# CortexM3_dev.net
KiCad netlist of a schematic drawn in Altium Designer
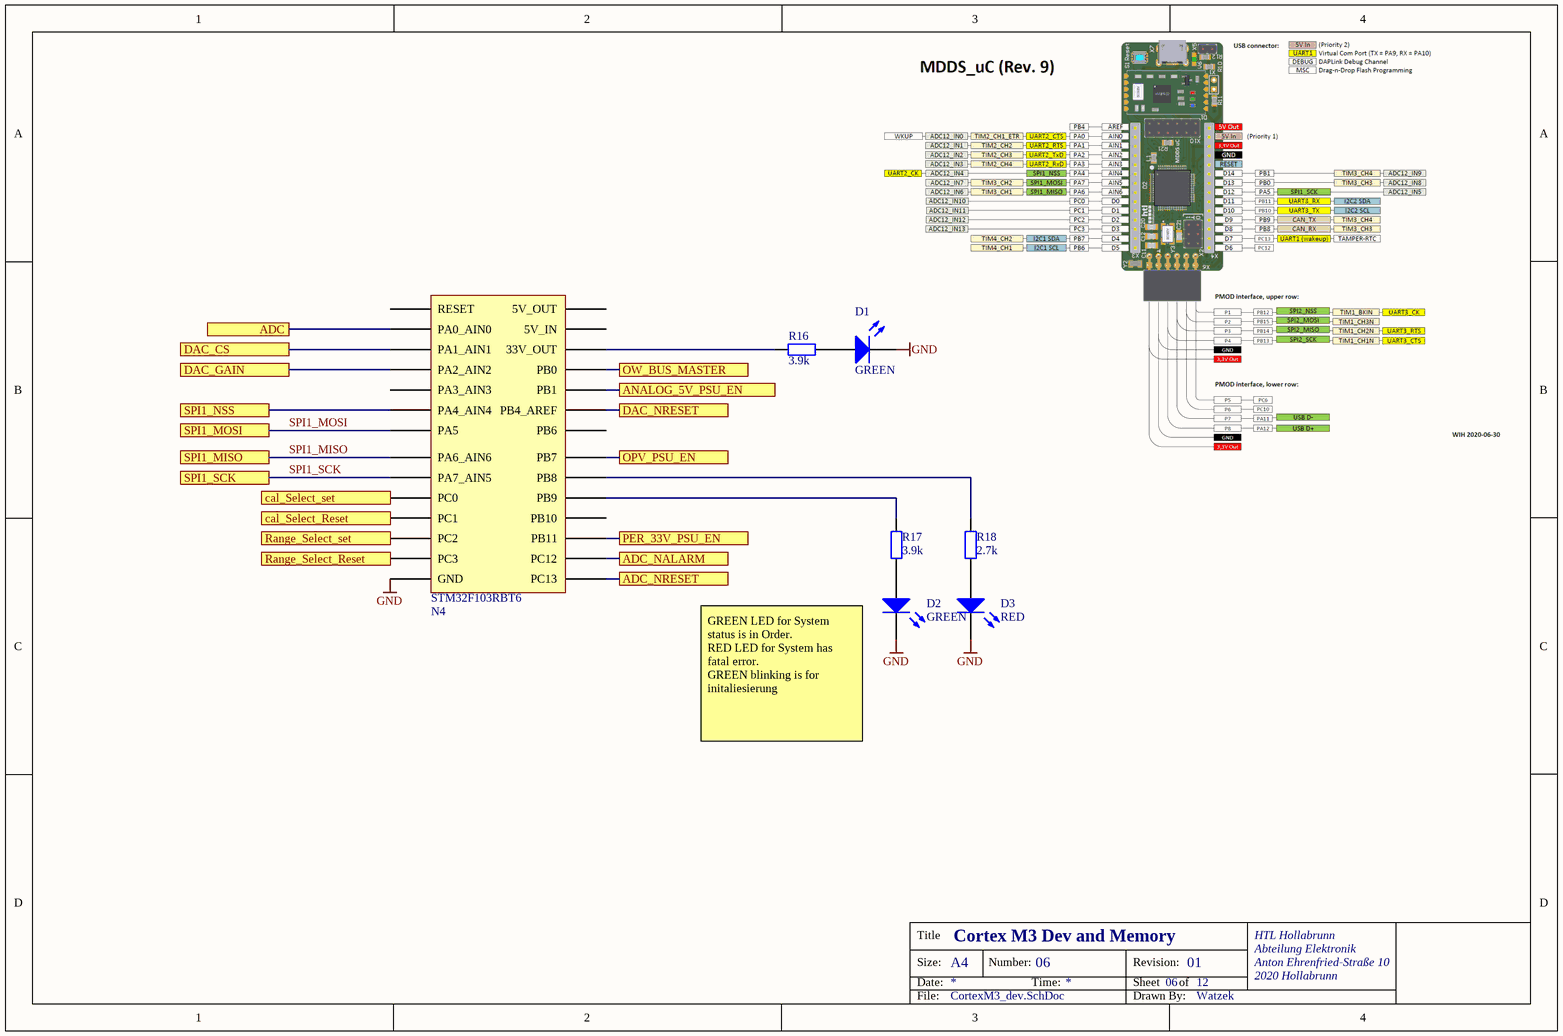
[diagram p0: CortexM3_dev.SchDoc]

(export (version "E")
  (design (tool "Eeschema 10.0.6"))
  (components
    (comp (ref "D1")
      (value "GREEN")
      (footprint "6-0805_N-KUE")
      (description "Typical INFRARED GaAs LED")
      (fields (field (name "PUBLISHER") "Altium Limited"))
      (libsource (lib "Miscellaneous Devices") (part "LED0"))
    )
    (comp (ref "D2")
      (value "GREEN")
      (footprint "6-0805_N-KUE")
      (description "Typical INFRARED GaAs LED")
      (fields (field (name "PUBLISHER") "Altium Limited"))
      (libsource (lib "Miscellaneous Devices") (part "LED0"))
    )
    (comp (ref "D3")
      (value "RED")
      (footprint "6-0805_N-KUE")
      (description "Typical INFRARED GaAs LED")
      (fields (field (name "PUBLISHER") "Altium Limited"))
      (libsource (lib "Miscellaneous Devices") (part "LED0"))
    )
    (comp (ref "N4") (value "STM32F103") (footprint "DIP28") (libsource (lib "STM_DEV") (part "STM32F103")))
    (comp (ref "R16")
      (value "3.9k")
      (footprint "C1206-KUE")
      (description "Resistor SMD")
      (fields (field (name "MANUFACTURER") "AVX") (field (name "PUBLISHER") "Altium Limited"))
      (libsource (lib "") (part "ResistorSMD_1"))
    )
    (comp (ref "R17")
      (value "3.9k")
      (footprint "C1206-KUE")
      (description "Resistor SMD")
      (fields (field (name "MANUFACTURER") "AVX") (field (name "PUBLISHER") "Altium Limited"))
      (libsource (lib "ExtrapartsKUE_V01") (part "ResistorSMD"))
    )
    (comp (ref "R18")
      (value "2.7k")
      (footprint "C1206-KUE")
      (description "Resistor SMD")
      (fields (field (name "MANUFACTURER") "AVX") (field (name "PUBLISHER") "Altium Limited"))
      (libsource (lib "ExtrapartsKUE_V01") (part "ResistorSMD"))
    )
  )
  (nets
    (net (code "1") (name "/ADC") (class "Default")
      (node (ref "N4") (pin "2") (pinfunction "PA0_AIN0_2") (pintype "passive"))
    )
    (net (code "2") (name "/ADC_NALARM") (class "Default")
      (node (ref "N4") (pin "28") (pinfunction "PC12_28") (pintype "passive"))
    )
    (net (code "3") (name "/ADC_NRESET") (class "Default")
      (node (ref "N4") (pin "27") (pinfunction "PC13_27") (pintype "passive"))
    )
    (net (code "4") (name "/ANALOG_5V_PSU_EN") (class "Default")
      (node (ref "N4") (pin "20") (pinfunction "PB1_20") (pintype "passive"))
    )
    (net (code "5") (name "/DAC_CS") (class "Default")
      (node (ref "N4") (pin "3") (pinfunction "PA1_AIN1_3") (pintype "passive"))
    )
    (net (code "6") (name "/DAC_GAIN") (class "Default")
      (node (ref "N4") (pin "4") (pinfunction "PA2_AIN2_4") (pintype "passive"))
    )
    (net (code "7") (name "/DAC_NRESET") (class "Default")
      (node (ref "N4") (pin "1") (pinfunction "PB4_AREF_1") (pintype "passive"))
    )
    (net (code "8") (name "/OPV_PSU_EN") (class "Default")
      (node (ref "N4") (pin "13") (pinfunction "PB7_13") (pintype "passive"))
    )
    (net (code "9") (name "/OW_BUS_MASTER") (class "Default")
      (node (ref "N4") (pin "21") (pinfunction "PB0_21") (pintype "passive"))
    )
    (net (code "10") (name "/PER_33V_PSU_EN") (class "Default")
      (node (ref "N4") (pin "23") (pinfunction "PB11_23") (pintype "passive"))
    )
    (net (code "11") (name "/Range_Select_Reset") (class "Default")
      (node (ref "N4") (pin "12") (pinfunction "PC3_12") (pintype "passive"))
    )
    (net (code "12") (name "/Range_Select_set") (class "Default")
      (node (ref "N4") (pin "11") (pinfunction "PC2_11") (pintype "passive"))
    )
    (net (code "13") (name "/SPI1_MISO") (class "Default")
      (node (ref "N4") (pin "8") (pinfunction "PA6_AIN6_8") (pintype "passive"))
    )
    (net (code "14") (name "/SPI1_MOSI") (class "Default")
      (node (ref "N4") (pin "22") (pinfunction "PA5_22") (pintype "passive"))
    )
    (net (code "15") (name "/SPI1_NSS") (class "Default")
      (node (ref "N4") (pin "6") (pinfunction "PA4_AIN4_6") (pintype "passive"))
    )
    (net (code "16") (name "/SPI1_SCK") (class "Default")
      (node (ref "N4") (pin "7") (pinfunction "PA7_AIN5_7") (pintype "passive"))
    )
    (net (code "17") (name "/cal_Select_Reset") (class "Default")
      (node (ref "N4") (pin "10") (pinfunction "PC1_10") (pintype "passive"))
    )
    (net (code "18") (name "/cal_Select_set") (class "Default")
      (node (ref "N4") (pin "9") (pinfunction "PC0_9") (pintype "passive"))
    )
    (net (code "19") (name "GND") (class "Default")
      (node (ref "D1") (pin "2") (pinfunction "K_2") (pintype "passive"))
      (node (ref "D2") (pin "2") (pinfunction "K_2") (pintype "passive"))
      (node (ref "D3") (pin "2") (pinfunction "K_2") (pintype "passive"))
      (node (ref "N4") (pin "18") (pinfunction "GND_18") (pintype "passive"))
    )
    (net (code "20") (name "Net-(D1-A)") (class "Default")
      (node (ref "D1") (pin "1") (pinfunction "A_1") (pintype "passive"))
      (node (ref "R16") (pin "2") (pinfunction "2_2") (pintype "passive"))
    )
    (net (code "21") (name "Net-(D2-A)") (class "Default")
      (node (ref "D2") (pin "1") (pinfunction "A_1") (pintype "passive"))
      (node (ref "R17") (pin "2") (pinfunction "2_2") (pintype "passive"))
    )
    (net (code "22") (name "Net-(D3-A)") (class "Default")
      (node (ref "D3") (pin "1") (pinfunction "A_1") (pintype "passive"))
      (node (ref "R18") (pin "2") (pinfunction "2_2") (pintype "passive"))
    )
    (net (code "23") (name "Net-(N4-33V_OUT)") (class "Default")
      (node (ref "N4") (pin "17") (pinfunction "33V_OUT_17") (pintype "passive"))
      (node (ref "R16") (pin "1") (pinfunction "1_1") (pintype "passive"))
    )
    (net (code "24") (name "Net-(N4-PB8)") (class "Default")
      (node (ref "N4") (pin "26") (pinfunction "PB8_26") (pintype "passive"))
      (node (ref "R18") (pin "1") (pinfunction "1_1") (pintype "passive"))
    )
    (net (code "25") (name "Net-(N4-PB9)") (class "Default")
      (node (ref "N4") (pin "25") (pinfunction "PB9_25") (pintype "passive"))
      (node (ref "R17") (pin "1") (pinfunction "1_1") (pintype "passive"))
    )
    (net (code "26") (name "unconnected-(N4-5V_IN-Pad16)") (class "Default")
      (node (ref "N4") (pin "16") (pinfunction "5V_IN_16") (pintype "passive"))
    )
    (net (code "27") (name "unconnected-(N4-5V_OUT-Pad15)") (class "Default")
      (node (ref "N4") (pin "15") (pinfunction "5V_OUT_15") (pintype "passive"))
    )
    (net (code "28") (name "unconnected-(N4-PA3_AIN3-Pad5)") (class "Default")
      (node (ref "N4") (pin "5") (pinfunction "PA3_AIN3_5") (pintype "passive"))
    )
    (net (code "29") (name "unconnected-(N4-PB6-Pad14)") (class "Default")
      (node (ref "N4") (pin "14") (pinfunction "PB6_14") (pintype "passive"))
    )
    (net (code "30") (name "unconnected-(N4-PB10-Pad24)") (class "Default")
      (node (ref "N4") (pin "24") (pinfunction "PB10_24") (pintype "passive"))
    )
    (net (code "31") (name "unconnected-(N4-RESET-Pad19)") (class "Default")
      (node (ref "N4") (pin "19") (pinfunction "RESET_19") (pintype "passive"))
    )
  )
)
